# MotorController.net
KiCad netlist of a schematic drawn in EAGLE
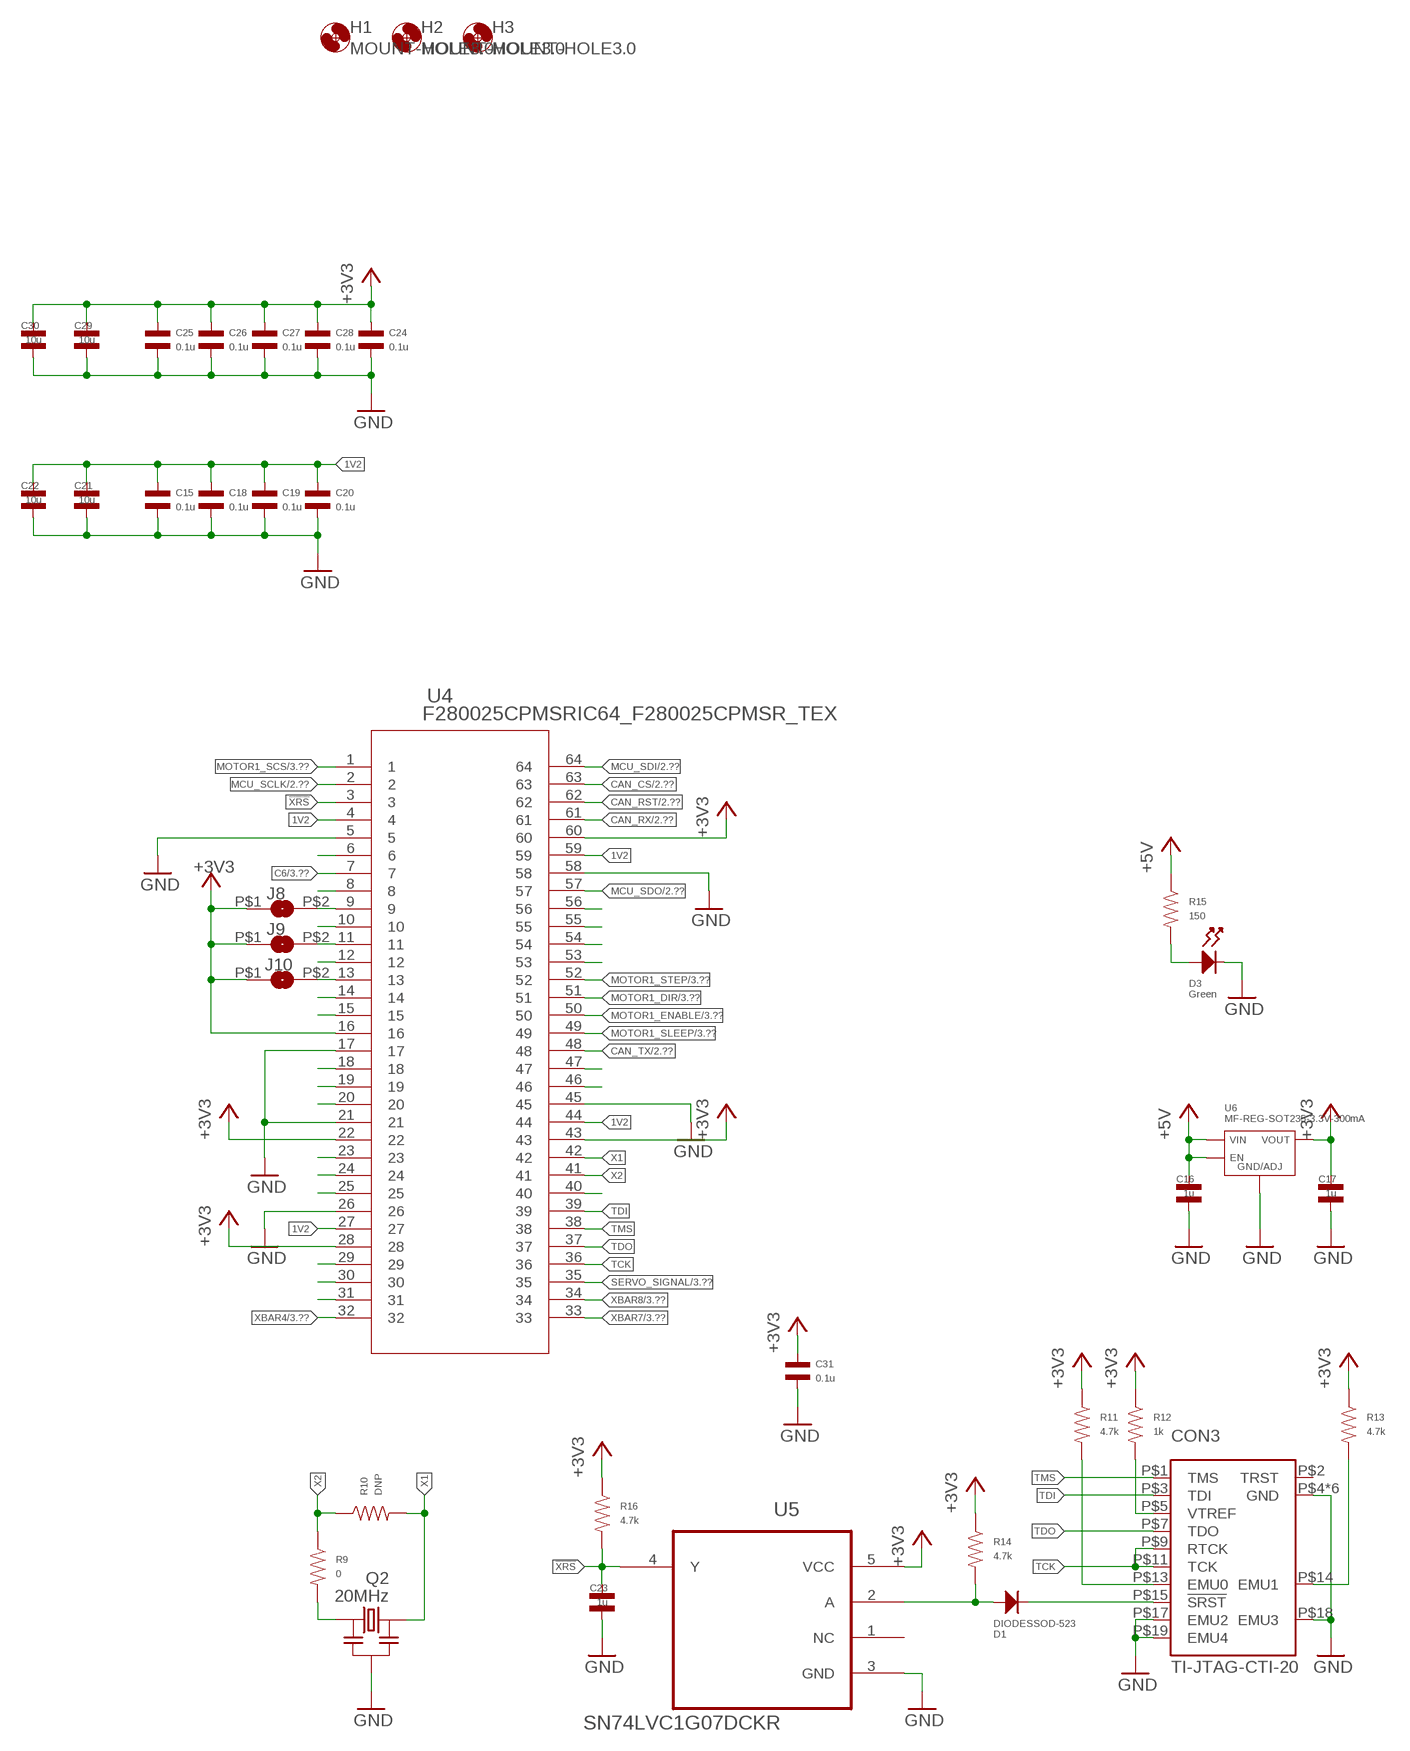
[diagram p0: schematic, sheet 1]
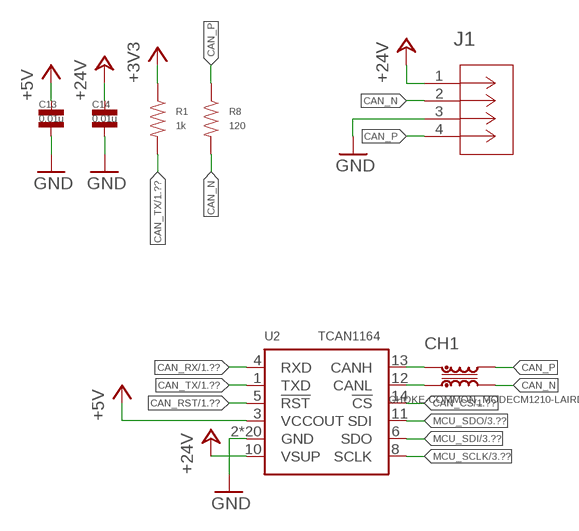
[diagram p1: schematic, sheet 2]
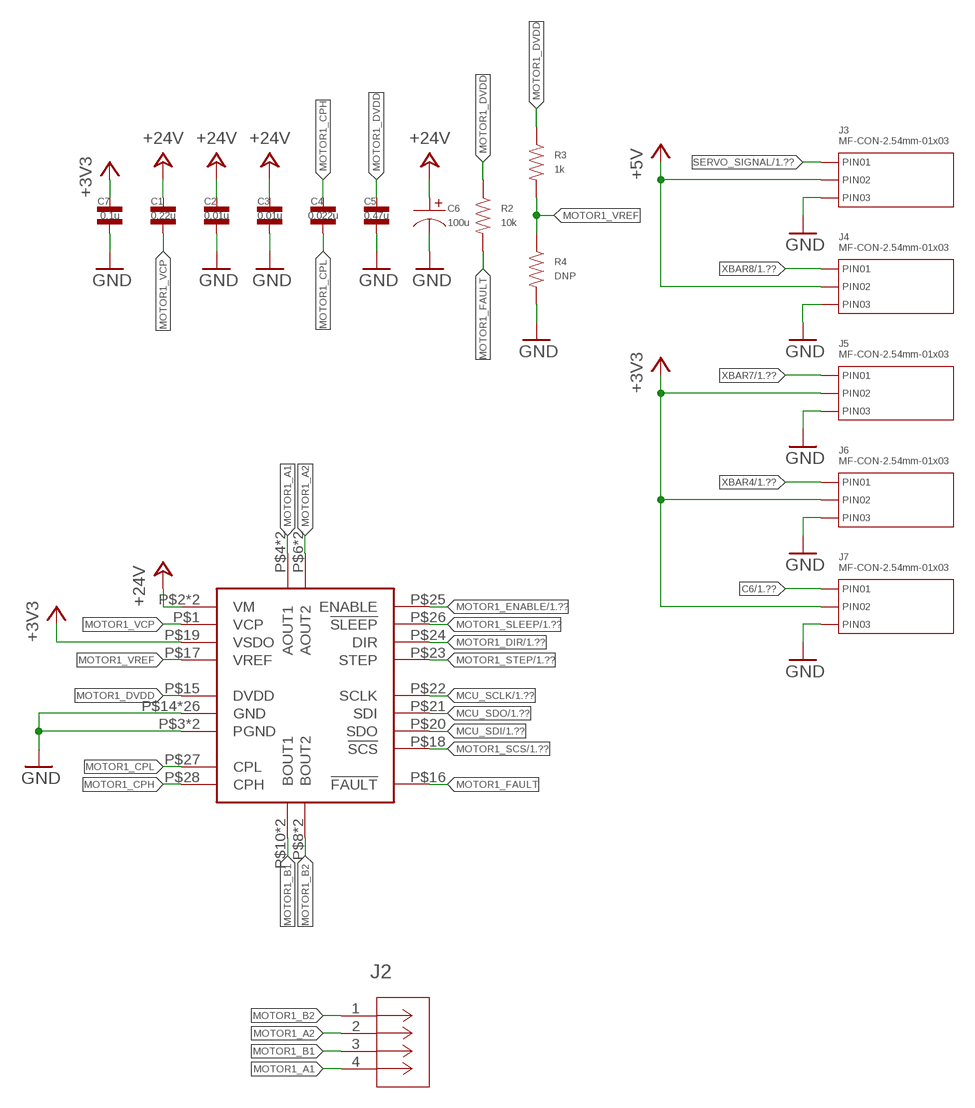
[diagram p2: schematic, sheet 3]

(export (version "E")
  (design (tool "Eeschema 10.0.6"))
  (components
    (comp (ref "C15")
      (value "0.1u")
      (footprint "eagle-import:C0402")
      (fields (field (name "MPN") "GCM155R71H104KE02D"))
      (libsource (lib "eagle-import") (part "CAPACITOR_NP_0402"))
    )
    (comp (ref "C16")
      (value "1u")
      (footprint "eagle-import:C0805")
      (fields (field (name "MPN") "CL21B105KAFNNNE"))
      (libsource (lib "eagle-import") (part "CAPACITOR_NP_0805"))
    )
    (comp (ref "C17")
      (value "1u")
      (footprint "eagle-import:C0805")
      (fields (field (name "MPN") "CL21B105KAFNNNE"))
      (libsource (lib "eagle-import") (part "CAPACITOR_NP_0805"))
    )
    (comp (ref "C18")
      (value "0.1u")
      (footprint "eagle-import:C0402")
      (fields (field (name "MPN") "GCM155R71H104KE02D"))
      (libsource (lib "eagle-import") (part "CAPACITOR_NP_0402"))
    )
    (comp (ref "C19")
      (value "0.1u")
      (footprint "eagle-import:C0402")
      (fields (field (name "MPN") "GCM155R71H104KE02D"))
      (libsource (lib "eagle-import") (part "CAPACITOR_NP_0402"))
    )
    (comp (ref "C20")
      (value "0.1u")
      (footprint "eagle-import:C0402")
      (fields (field (name "MPN") "GCM155R71H104KE02D"))
      (libsource (lib "eagle-import") (part "CAPACITOR_NP_0402"))
    )
    (comp (ref "C21")
      (value "10u")
      (footprint "eagle-import:C0805")
      (fields (field (name "MPN") "CL21A106KAYNNNE"))
      (libsource (lib "eagle-import") (part "CAPACITOR_NP_0805"))
    )
    (comp (ref "C22")
      (value "10u")
      (footprint "eagle-import:C0805")
      (fields (field (name "MPN") "CL21A106KAYNNNE"))
      (libsource (lib "eagle-import") (part "CAPACITOR_NP_0805"))
    )
    (comp (ref "C23")
      (value "1u")
      (footprint "eagle-import:C0402")
      (fields (field (name "MPN") "CL05A105KA5NQNC"))
      (libsource (lib "eagle-import") (part "CAPACITOR_NP_0402"))
    )
    (comp (ref "C24")
      (value "0.1u")
      (footprint "eagle-import:C0402")
      (fields (field (name "MPN") "GCM155R71H104KE02D"))
      (libsource (lib "eagle-import") (part "CAPACITOR_NP_0402"))
    )
    (comp (ref "C25")
      (value "0.1u")
      (footprint "eagle-import:C0402")
      (fields (field (name "MPN") "GCM155R71H104KE02D"))
      (libsource (lib "eagle-import") (part "CAPACITOR_NP_0402"))
    )
    (comp (ref "C26")
      (value "0.1u")
      (footprint "eagle-import:C0402")
      (fields (field (name "MPN") "GCM155R71H104KE02D"))
      (libsource (lib "eagle-import") (part "CAPACITOR_NP_0402"))
    )
    (comp (ref "C27")
      (value "0.1u")
      (footprint "eagle-import:C0402")
      (fields (field (name "MPN") "GCM155R71H104KE02D"))
      (libsource (lib "eagle-import") (part "CAPACITOR_NP_0402"))
    )
    (comp (ref "C28")
      (value "0.1u")
      (footprint "eagle-import:C0402")
      (fields (field (name "MPN") "GCM155R71H104KE02D"))
      (libsource (lib "eagle-import") (part "CAPACITOR_NP_0402"))
    )
    (comp (ref "C29")
      (value "10u")
      (footprint "eagle-import:C0805")
      (fields (field (name "MPN") "CL21A106KAYNNNE"))
      (libsource (lib "eagle-import") (part "CAPACITOR_NP_0805"))
    )
    (comp (ref "C30")
      (value "10u")
      (footprint "eagle-import:C0805")
      (fields (field (name "MPN") "CL21A106KAYNNNE"))
      (libsource (lib "eagle-import") (part "CAPACITOR_NP_0805"))
    )
    (comp (ref "C31")
      (value "0.1u")
      (footprint "eagle-import:C0402")
      (fields (field (name "MPN") "GCM155R71H104KE02D"))
      (libsource (lib "eagle-import") (part "MF_Passives_4704077_CAPACITOR_NP_0402"))
    )
    (comp (ref "CON3")
      (value "TI-JTAG-CTI-20")
      (footprint "eagle-import:FTR-110-51-L-D-06")
      (fields (field (name "MPN") "FTR-110-51-L-D-06"))
      (libsource (lib "eagle-import") (part "TI-JTAG-CTI-20"))
    )
    (comp (ref "D1")
      (value "DIODESSOD-523")
      (footprint "eagle-import:SOD523")
      (fields (field (name "MPN") "RB510SM-40FHT2R"))
      (libsource (lib "eagle-import") (part "DIODESSOD-523"))
    )
    (comp (ref "D3")
      (value "Green")
      (footprint "eagle-import:LED0603")
      (fields (field (name "HOUSEPART") "NO") (field (name "MPN") "SML-E12P8WT86"))
      (libsource (lib "eagle-import") (part "LED_SINGLE-0603"))
    )
    (comp (ref "H1")
      (value "MOUNT-HOLE3.0")
      (footprint "eagle-import:3,0")
      (libsource (lib "eagle-import") (part "MOUNT-HOLE3.0"))
    )
    (comp (ref "H2")
      (value "MOUNT-HOLE3.0")
      (footprint "eagle-import:3,0")
      (libsource (lib "eagle-import") (part "MOUNT-HOLE3.0"))
    )
    (comp (ref "H3")
      (value "MOUNT-HOLE3.0")
      (footprint "eagle-import:3,0")
      (libsource (lib "eagle-import") (part "MOUNT-HOLE3.0"))
    )
    (comp (ref "J8")
      (value "JUMPER")
      (footprint "eagle-import:SJ")
      (libsource (lib "eagle-import") (part "JUMPER"))
    )
    (comp (ref "J9")
      (value "JUMPER")
      (footprint "eagle-import:SJ")
      (libsource (lib "eagle-import") (part "JUMPER"))
    )
    (comp (ref "J10")
      (value "JUMPER")
      (footprint "eagle-import:SJ")
      (libsource (lib "eagle-import") (part "JUMPER"))
    )
    (comp (ref "Q2")
      (value "20MHz")
      (footprint "eagle-import:CSTNE")
      (fields (field (name "MPN") "CSTNE20M0V53C000R0"))
      (libsource (lib "eagle-import") (part "RESONATORCSTNE"))
    )
    (comp (ref "R9")
      (value "0")
      (footprint "eagle-import:R0402")
      (fields (field (name "MPN") "ERJ-2GE0R00X"))
      (libsource (lib "eagle-import") (part "RESISTOR_0402"))
    )
    (comp (ref "R10")
      (value "DNP")
      (footprint "eagle-import:R0402")
      (libsource (lib "eagle-import") (part "RESISTOR_0402"))
    )
    (comp (ref "R11")
      (value "4.7k")
      (footprint "eagle-import:R0402")
      (fields (field (name "MPN") "ERJ-2RKF4701X"))
      (libsource (lib "eagle-import") (part "RESISTOR_0402"))
    )
    (comp (ref "R12")
      (value "1k")
      (footprint "eagle-import:R0402")
      (fields (field (name "MPN") "ERJ-2RKF1001X"))
      (libsource (lib "eagle-import") (part "RESISTOR_0402"))
    )
    (comp (ref "R13")
      (value "4.7k")
      (footprint "eagle-import:R0402")
      (fields (field (name "MPN") "ERJ-2RKF4701X"))
      (libsource (lib "eagle-import") (part "RESISTOR_0402"))
    )
    (comp (ref "R14")
      (value "4.7k")
      (footprint "eagle-import:R0402")
      (fields (field (name "MPN") "ERJ-2RKF4701X"))
      (libsource (lib "eagle-import") (part "RESISTOR_0402"))
    )
    (comp (ref "R15")
      (value "150")
      (footprint "eagle-import:R0805")
      (fields (field (name "MPN") "ERJ-6GEYJ151V"))
      (libsource (lib "eagle-import") (part "RESISTOR_0805"))
    )
    (comp (ref "R16")
      (value "4.7k")
      (footprint "eagle-import:R0402")
      (fields (field (name "MPN") "ERJ-2RKF4701X"))
      (libsource (lib "eagle-import") (part "RESISTOR_0402"))
    )
    (comp (ref "U4")
      (value "F280025CPMSRIC64_F280025CPMSR_TEX")
      (footprint "eagle-import:IC64_F280025CPMSR_TEX")
      (fields
        (field (name "MANUFACTURER_PART_NUMBER") "F280025CPMSR")
        (field (name "COPYRIGHT") "Copyright (C) 2024 Ultra Librarian. All rights reserved.")
      )
      (libsource (lib "eagle-import") (part "F280025CPMSRIC64_F280025CPMSR_TEX"))
    )
    (comp (ref "U5")
      (value "SN74LVC1G07DCKR")
      (footprint "eagle-import:SOT65P210X110-5N")
      (libsource (lib "eagle-import") (part "SN74LVC1G07DCKR"))
    )
    (comp (ref "U6")
      (value "MF-REG-SOT235-3.3V-300mA")
      (footprint "eagle-import:SOT-23-5")
      (fields (field (name "HOUSEPART") "YES") (field (name "MPN") "TLV70233PDBVR"))
      (libsource (lib "eagle-import") (part "TLV70233PDBVR"))
    )
    (comp (ref "C13")
      (value "0.01u")
      (footprint "eagle-import:C0402")
      (fields (field (name "MPN") "CL05B103KB5NNNC"))
      (libsource (lib "eagle-import") (part "CAPACITOR_NP_0402"))
    )
    (comp (ref "C14")
      (value "0.01u")
      (footprint "eagle-import:C0402")
      (fields (field (name "MPN") "CL05B103KB5NNNC"))
      (libsource (lib "eagle-import") (part "CAPACITOR_NP_0402"))
    )
    (comp (ref "CH1")
      (value "CHOKE-COMMON_MODECM1210-LAIRD")
      (footprint "eagle-import:CM1210-LAIRD")
      (fields (field (name "MPN") "CM1210B104R-1A"))
      (libsource (lib "eagle-import") (part "CHOKE-COMMON_MODECM1210-LAIRD"))
    )
    (comp (ref "J1")
      (value "768250004CON_768250004_MOL")
      (footprint "eagle-import:CON_768250004_MOL")
      (fields
        (field (name "MANUFACTURER_PART_NUMBER") "768250004")
        (field (name "MPN") "0768250004")
        (field (name "COPYRIGHT") "Copyright (C) 2024 Ultra Librarian. All rights reserved.")
      )
      (libsource (lib "eagle-import") (part "768250004CON_768250004_MOL"))
    )
    (comp (ref "R1")
      (value "1k")
      (footprint "eagle-import:R0402")
      (fields (field (name "MPN") "ERJ-2RKF1001X"))
      (libsource (lib "eagle-import") (part "RESISTOR_0402"))
    )
    (comp (ref "R8")
      (value "120")
      (footprint "eagle-import:R0402")
      (fields (field (name "MPN") "ERJ-2GEJ121X"))
      (libsource (lib "eagle-import") (part "RESISTOR_0402"))
    )
    (comp (ref "U2")
      (value "TCAN1164")
      (footprint "eagle-import:CONV_TPS63021DSJ")
      (fields (field (name "MPN") "TCAN1164DMTRQ1"))
      (libsource (lib "eagle-import") (part "TCAN1164"))
    )
    (comp (ref "C1")
      (value "0.22u")
      (footprint "eagle-import:C0402")
      (fields (field (name "MPN") "CL05B224KA5VPNC"))
      (libsource (lib "eagle-import") (part "CAPACITOR_NP_0402"))
    )
    (comp (ref "C2")
      (value "0.01u")
      (footprint "eagle-import:C0402")
      (fields (field (name "MPN") "CL05B103KB5NNNC"))
      (libsource (lib "eagle-import") (part "CAPACITOR_NP_0402"))
    )
    (comp (ref "C3")
      (value "0.01u")
      (footprint "eagle-import:C0402")
      (fields (field (name "MPN") "CL05B103KB5NNNC"))
      (libsource (lib "eagle-import") (part "CAPACITOR_NP_0402"))
    )
    (comp (ref "C4")
      (value "0.022u")
      (footprint "eagle-import:C0402")
      (fields (field (name "MPN") "CL05B223KB5VPNC"))
      (libsource (lib "eagle-import") (part "CAPACITOR_NP_0402"))
    )
    (comp (ref "C5")
      (value "0.47u")
      (footprint "eagle-import:C0402")
      (fields (field (name "MPN") "CL05A474KA5NNNC"))
      (libsource (lib "eagle-import") (part "CAPACITOR_NP_0402"))
    )
    (comp (ref "C6")
      (value "100u")
      (footprint "eagle-import:CP6.3MM")
      (fields (field (name "MPN") "MAL218297603E3"))
      (libsource (lib "eagle-import") (part "CAPACITOR_P_6.3MM"))
    )
    (comp (ref "C7")
      (value "0.1u")
      (footprint "eagle-import:C0402")
      (fields (field (name "MPN") "GCM155R71H104KE02D"))
      (libsource (lib "eagle-import") (part "CAPACITOR_NP_0402"))
    )
    (comp (ref "J2")
      (value "768250004CON_768250004_MOL")
      (footprint "eagle-import:CON_768250004_MOL")
      (fields
        (field (name "MANUFACTURER_PART_NUMBER") "768250004")
        (field (name "MPN") "0768250004")
        (field (name "COPYRIGHT") "Copyright (C) 2024 Ultra Librarian. All rights reserved.")
      )
      (libsource (lib "eagle-import") (part "768250004CON_768250004_MOL"))
    )
    (comp (ref "J3")
      (value "MF-CON-2.54mm-01x03")
      (footprint "eagle-import:PTH_2.54MM_01X03")
      (fields (field (name "HOUSEPART") "YES"))
      (libsource (lib "eagle-import") (part "CON_01X03_PTH_2.54MM"))
    )
    (comp (ref "J4")
      (value "MF-CON-2.54mm-01x03")
      (footprint "eagle-import:PTH_2.54MM_01X03")
      (fields (field (name "HOUSEPART") "YES"))
      (libsource (lib "eagle-import") (part "CON_01X03_PTH_2.54MM"))
    )
    (comp (ref "J5")
      (value "MF-CON-2.54mm-01x03")
      (footprint "eagle-import:PTH_2.54MM_01X03")
      (fields (field (name "HOUSEPART") "YES"))
      (libsource (lib "eagle-import") (part "CON_01X03_PTH_2.54MM"))
    )
    (comp (ref "J6")
      (value "MF-CON-2.54mm-01x03")
      (footprint "eagle-import:PTH_2.54MM_01X03")
      (fields (field (name "HOUSEPART") "YES"))
      (libsource (lib "eagle-import") (part "CON_01X03_PTH_2.54MM"))
    )
    (comp (ref "J7")
      (value "MF-CON-2.54mm-01x03")
      (footprint "eagle-import:PTH_2.54MM_01X03")
      (fields (field (name "HOUSEPART") "YES"))
      (libsource (lib "eagle-import") (part "CON_01X03_PTH_2.54MM"))
    )
    (comp (ref "R2")
      (value "10k")
      (footprint "eagle-import:R0402")
      (fields (field (name "MPN") "ERJ-2RKF1002X"))
      (libsource (lib "eagle-import") (part "RESISTOR_0402"))
    )
    (comp (ref "R3")
      (value "1k")
      (footprint "eagle-import:R0402")
      (fields (field (name "MPN") "ERJ-2RKF1001X"))
      (libsource (lib "eagle-import") (part "RESISTOR_0402"))
    )
    (comp (ref "R4")
      (value "DNP")
      (footprint "eagle-import:R0402")
      (libsource (lib "eagle-import") (part "RESISTOR_0402"))
    )
    (comp (ref "U1")
      (value "DRV8434SPWPR")
      (footprint "eagle-import:HTSSOP(PWP)-28")
      (libsource (lib "eagle-import") (part "DRV8434SPWPR"))
    )
  )
  (nets
    (net (code "1") (name "+3V3") (class "Default")
      (node (ref "C17") (pin "P$1") (pinfunction "P$1_P$1") (pintype "passive"))
      (node (ref "C24") (pin "P$1") (pinfunction "P$1_P$1") (pintype "passive"))
      (node (ref "C25") (pin "P$1") (pinfunction "P$1_P$1") (pintype "passive"))
      (node (ref "C26") (pin "P$1") (pinfunction "P$1_P$1") (pintype "passive"))
      (node (ref "C27") (pin "P$1") (pinfunction "P$1_P$1") (pintype "passive"))
      (node (ref "C28") (pin "P$1") (pinfunction "P$1_P$1") (pintype "passive"))
      (node (ref "C29") (pin "P$1") (pinfunction "P$1_P$1") (pintype "passive"))
      (node (ref "C30") (pin "P$1") (pinfunction "P$1_P$1") (pintype "passive"))
      (node (ref "C31") (pin "P$1") (pinfunction "P$1_P$1") (pintype "passive"))
      (node (ref "C7") (pin "P$1") (pinfunction "P$1_P$1") (pintype "passive"))
      (node (ref "J10") (pin "P$1") (pinfunction "1_P$1") (pintype "passive"))
      (node (ref "J5") (pin "P$2") (pinfunction "PIN2_P$2") (pintype "bidirectional"))
      (node (ref "J6") (pin "P$2") (pinfunction "PIN2_P$2") (pintype "bidirectional"))
      (node (ref "J7") (pin "P$2") (pinfunction "PIN2_P$2") (pintype "bidirectional"))
      (node (ref "J8") (pin "P$1") (pinfunction "1_P$1") (pintype "passive"))
      (node (ref "J9") (pin "P$1") (pinfunction "1_P$1") (pintype "passive"))
      (node (ref "R1") (pin "P$1") (pinfunction "P$1_P$1") (pintype "passive"))
      (node (ref "R11") (pin "P$1") (pinfunction "P$1_P$1") (pintype "passive"))
      (node (ref "R12") (pin "P$1") (pinfunction "P$1_P$1") (pintype "passive"))
      (node (ref "R13") (pin "P$1") (pinfunction "P$1_P$1") (pintype "passive"))
      (node (ref "R14") (pin "P$1") (pinfunction "P$1_P$1") (pintype "passive"))
      (node (ref "R16") (pin "P$1") (pinfunction "P$1_P$1") (pintype "passive"))
      (node (ref "U1") (pin "P$19") (pinfunction "VSDO_P$19") (pintype "bidirectional"))
      (node (ref "U4") (pin "16") (pinfunction "16_16") (pintype "passive"))
      (node (ref "U4") (pin "22") (pinfunction "22_22") (pintype "passive"))
      (node (ref "U4") (pin "28") (pinfunction "28_28") (pintype "passive"))
      (node (ref "U4") (pin "43") (pinfunction "43_43") (pintype "passive"))
      (node (ref "U4") (pin "60") (pinfunction "60_60") (pintype "passive"))
      (node (ref "U5") (pin "5") (pinfunction "VCC_5") (pintype "power_in"))
      (node (ref "U6") (pin "P$5") (pinfunction "VOUT_P$5") (pintype "bidirectional"))
    )
    (net (code "2") (name "+5V") (class "Default")
      (node (ref "C13") (pin "P$1") (pinfunction "P$1_P$1") (pintype "passive"))
      (node (ref "C16") (pin "P$1") (pinfunction "P$1_P$1") (pintype "passive"))
      (node (ref "J3") (pin "P$2") (pinfunction "PIN2_P$2") (pintype "bidirectional"))
      (node (ref "J4") (pin "P$2") (pinfunction "PIN2_P$2") (pintype "bidirectional"))
      (node (ref "R15") (pin "P$1") (pinfunction "P$1_P$1") (pintype "passive"))
      (node (ref "U2") (pin "3") (pinfunction "VCCOUT_3") (pintype "bidirectional"))
      (node (ref "U6") (pin "P$1") (pinfunction "VIN_P$1") (pintype "bidirectional"))
      (node (ref "U6") (pin "P$3") (pinfunction "EN_P$3") (pintype "bidirectional"))
    )
    (net (code "3") (name "+24V") (class "Default")
      (node (ref "C1") (pin "P$1") (pinfunction "P$1_P$1") (pintype "passive"))
      (node (ref "C14") (pin "P$1") (pinfunction "P$1_P$1") (pintype "passive"))
      (node (ref "C2") (pin "P$1") (pinfunction "P$1_P$1") (pintype "passive"))
      (node (ref "C3") (pin "P$1") (pinfunction "P$1_P$1") (pintype "passive"))
      (node (ref "C6") (pin "P$1") (pinfunction "P$1_P$1") (pintype "passive"))
      (node (ref "J1") (pin "1") (pinfunction "1_1") (pintype "passive"))
      (node (ref "U1") (pin "P$13") (pinfunction "VM_P$13") (pintype "bidirectional"))
      (node (ref "U1") (pin "P$2") (pinfunction "VM_P$2") (pintype "bidirectional"))
      (node (ref "U2") (pin "10") (pinfunction "VSUP_10") (pintype "bidirectional"))
    )
    (net (code "4") (name "1V2") (class "Default")
      (node (ref "C15") (pin "P$1") (pinfunction "P$1_P$1") (pintype "passive"))
      (node (ref "C18") (pin "P$1") (pinfunction "P$1_P$1") (pintype "passive"))
      (node (ref "C19") (pin "P$1") (pinfunction "P$1_P$1") (pintype "passive"))
      (node (ref "C20") (pin "P$1") (pinfunction "P$1_P$1") (pintype "passive"))
      (node (ref "C21") (pin "P$1") (pinfunction "P$1_P$1") (pintype "passive"))
      (node (ref "C22") (pin "P$1") (pinfunction "P$1_P$1") (pintype "passive"))
      (node (ref "U4") (pin "27") (pinfunction "27_27") (pintype "passive"))
      (node (ref "U4") (pin "4") (pinfunction "4_4") (pintype "passive"))
      (node (ref "U4") (pin "44") (pinfunction "44_44") (pintype "passive"))
      (node (ref "U4") (pin "59") (pinfunction "59_59") (pintype "passive"))
    )
    (net (code "5") (name "C6") (class "Default")
      (node (ref "J7") (pin "P$1") (pinfunction "PIN1_P$1") (pintype "bidirectional"))
      (node (ref "U4") (pin "7") (pinfunction "7_7") (pintype "passive"))
    )
    (net (code "6") (name "CAN_CS") (class "Default")
      (node (ref "U2") (pin "14") (pinfunction "~{CS}_14") (pintype "bidirectional"))
      (node (ref "U4") (pin "63") (pinfunction "63_63") (pintype "passive"))
    )
    (net (code "7") (name "CAN_N") (class "Default")
      (node (ref "CH1") (pin "P$3") (pinfunction "3_P$3") (pintype "bidirectional"))
      (node (ref "J1") (pin "2") (pinfunction "2_2") (pintype "passive"))
      (node (ref "R8") (pin "P$2") (pinfunction "P$2_P$2") (pintype "passive"))
    )
    (net (code "8") (name "CAN_P") (class "Default")
      (node (ref "CH1") (pin "P$2") (pinfunction "2_P$2") (pintype "bidirectional"))
      (node (ref "J1") (pin "4") (pinfunction "4_4") (pintype "passive"))
      (node (ref "R8") (pin "P$1") (pinfunction "P$1_P$1") (pintype "passive"))
    )
    (net (code "9") (name "CAN_RST") (class "Default")
      (node (ref "U2") (pin "5") (pinfunction "~{RST}_5") (pintype "bidirectional"))
      (node (ref "U4") (pin "62") (pinfunction "62_62") (pintype "passive"))
    )
    (net (code "10") (name "CAN_RX") (class "Default")
      (node (ref "U2") (pin "4") (pinfunction "RXD_4") (pintype "bidirectional"))
      (node (ref "U4") (pin "61") (pinfunction "61_61") (pintype "passive"))
    )
    (net (code "11") (name "CAN_TX") (class "Default")
      (node (ref "R1") (pin "P$2") (pinfunction "P$2_P$2") (pintype "passive"))
      (node (ref "U2") (pin "1") (pinfunction "TXD_1") (pintype "bidirectional"))
      (node (ref "U4") (pin "48") (pinfunction "48_48") (pintype "passive"))
    )
    (net (code "12") (name "GND") (class "Default")
      (node (ref "C13") (pin "P$2") (pinfunction "P$2_P$2") (pintype "passive"))
      (node (ref "C14") (pin "P$2") (pinfunction "P$2_P$2") (pintype "passive"))
      (node (ref "C15") (pin "P$2") (pinfunction "P$2_P$2") (pintype "passive"))
      (node (ref "C16") (pin "P$2") (pinfunction "P$2_P$2") (pintype "passive"))
      (node (ref "C17") (pin "P$2") (pinfunction "P$2_P$2") (pintype "passive"))
      (node (ref "C18") (pin "P$2") (pinfunction "P$2_P$2") (pintype "passive"))
      (node (ref "C19") (pin "P$2") (pinfunction "P$2_P$2") (pintype "passive"))
      (node (ref "C2") (pin "P$2") (pinfunction "P$2_P$2") (pintype "passive"))
      (node (ref "C20") (pin "P$2") (pinfunction "P$2_P$2") (pintype "passive"))
      (node (ref "C21") (pin "P$2") (pinfunction "P$2_P$2") (pintype "passive"))
      (node (ref "C22") (pin "P$2") (pinfunction "P$2_P$2") (pintype "passive"))
      (node (ref "C23") (pin "P$2") (pinfunction "P$2_P$2") (pintype "passive"))
      (node (ref "C24") (pin "P$2") (pinfunction "P$2_P$2") (pintype "passive"))
      (node (ref "C25") (pin "P$2") (pinfunction "P$2_P$2") (pintype "passive"))
      (node (ref "C26") (pin "P$2") (pinfunction "P$2_P$2") (pintype "passive"))
      (node (ref "C27") (pin "P$2") (pinfunction "P$2_P$2") (pintype "passive"))
      (node (ref "C28") (pin "P$2") (pinfunction "P$2_P$2") (pintype "passive"))
      (node (ref "C29") (pin "P$2") (pinfunction "P$2_P$2") (pintype "passive"))
      (node (ref "C3") (pin "P$2") (pinfunction "P$2_P$2") (pintype "passive"))
      (node (ref "C30") (pin "P$2") (pinfunction "P$2_P$2") (pintype "passive"))
      (node (ref "C31") (pin "P$2") (pinfunction "P$2_P$2") (pintype "passive"))
      (node (ref "C5") (pin "P$2") (pinfunction "P$2_P$2") (pintype "passive"))
      (node (ref "C6") (pin "P$2") (pinfunction "P$2_P$2") (pintype "passive"))
      (node (ref "C7") (pin "P$2") (pinfunction "P$2_P$2") (pintype "passive"))
      (node (ref "CON3") (pin "P$10") (pinfunction "GND_P$10") (pintype "bidirectional"))
      (node (ref "CON3") (pin "P$12") (pinfunction "GND_P$12") (pintype "bidirectional"))
      (node (ref "CON3") (pin "P$16") (pinfunction "GND_P$16") (pintype "bidirectional"))
      (node (ref "CON3") (pin "P$17") (pinfunction "EMU2_P$17") (pintype "bidirectional"))
      (node (ref "CON3") (pin "P$18") (pinfunction "EMU3_P$18") (pintype "bidirectional"))
      (node (ref "CON3") (pin "P$19") (pinfunction "EMU4_P$19") (pintype "bidirectional"))
      (node (ref "CON3") (pin "P$20") (pinfunction "GND_P$20") (pintype "bidirectional"))
      (node (ref "CON3") (pin "P$4") (pinfunction "GND_P$4") (pintype "bidirectional"))
      (node (ref "CON3") (pin "P$8") (pinfunction "GND_P$8") (pintype "bidirectional"))
      (node (ref "D3") (pin "CATHODE") (pinfunction "CATHODE_CATHODE") (pintype "power_in"))
      (node (ref "J1") (pin "3") (pinfunction "3_3") (pintype "passive"))
      (node (ref "J3") (pin "P$3") (pinfunction "PIN3_P$3") (pintype "bidirectional"))
      (node (ref "J4") (pin "P$3") (pinfunction "PIN3_P$3") (pintype "bidirectional"))
      (node (ref "J5") (pin "P$3") (pinfunction "PIN3_P$3") (pintype "bidirectional"))
      (node (ref "J6") (pin "P$3") (pinfunction "PIN3_P$3") (pintype "bidirectional"))
      (node (ref "J7") (pin "P$3") (pinfunction "PIN3_P$3") (pintype "bidirectional"))
      (node (ref "Q2") (pin "2") (pinfunction "GND_2") (pintype "passive"))
      (node (ref "R4") (pin "P$2") (pinfunction "P$2_P$2") (pintype "passive"))
      (node (ref "U1") (pin "P$12") (pinfunction "PGND_P$12") (pintype "bidirectional"))
      (node (ref "U1") (pin "P$14") (pinfunction "GND_P$14") (pintype "bidirectional"))
      (node (ref "U1") (pin "P$29") (pinfunction "GND_P$29") (pintype "bidirectional"))
      (node (ref "U1") (pin "P$3") (pinfunction "PGND_P$3") (pintype "bidirectional"))
      (node (ref "U1") (pin "P$30") (pinfunction "GND_P$30") (pintype "bidirectional"))
      (node (ref "U1") (pin "P$31") (pinfunction "GND_P$31") (pintype "bidirectional"))
      (node (ref "U1") (pin "P$32") (pinfunction "GND_P$32") (pintype "bidirectional"))
      (node (ref "U1") (pin "P$33") (pinfunction "GND_P$33") (pintype "bidirectional"))
      (node (ref "U1") (pin "P$34") (pinfunction "GND_P$34") (pintype "bidirectional"))
      (node (ref "U1") (pin "P$35") (pinfunction "GND_P$35") (pintype "bidirectional"))
      (node (ref "U1") (pin "P$36") (pinfunction "GND_P$36") (pintype "bidirectional"))
      (node (ref "U1") (pin "P$37") (pinfunction "GND_P$37") (pintype "bidirectional"))
      (node (ref "U1") (pin "P$38") (pinfunction "GND_P$38") (pintype "bidirectional"))
      (node (ref "U1") (pin "P$39") (pinfunction "GND_P$39") (pintype "bidirectional"))
      (node (ref "U1") (pin "P$40") (pinfunction "GND_P$40") (pintype "bidirectional"))
      (node (ref "U1") (pin "P$41") (pinfunction "GND_P$41") (pintype "bidirectional"))
      (node (ref "U1") (pin "P$42") (pinfunction "GND_P$42") (pintype "bidirectional"))
      (node (ref "U1") (pin "P$43") (pinfunction "GND_P$43") (pintype "bidirectional"))
      (node (ref "U1") (pin "P$44") (pinfunction "GND_P$44") (pintype "bidirectional"))
      (node (ref "U1") (pin "P$45") (pinfunction "GND_P$45") (pintype "bidirectional"))
      (node (ref "U1") (pin "P$46") (pinfunction "GND_P$46") (pintype "bidirectional"))
      (node (ref "U1") (pin "P$47") (pinfunction "GND_P$47") (pintype "bidirectional"))
      (node (ref "U1") (pin "P$48") (pinfunction "GND_P$48") (pintype "bidirectional"))
      (node (ref "U1") (pin "P$49") (pinfunction "GND_P$49") (pintype "bidirectional"))
      (node (ref "U1") (pin "P$50") (pinfunction "GND_P$50") (pintype "bidirectional"))
      (node (ref "U1") (pin "P$51") (pinfunction "GND_P$51") (pintype "bidirectional"))
      (node (ref "U1") (pin "P$52") (pinfunction "GND_P$52") (pintype "bidirectional"))
      (node (ref "U1") (pin "P$53") (pinfunction "GND_P$53") (pintype "bidirectional"))
      (node (ref "U2") (pin "15") (pinfunction "GND_15") (pintype "bidirectional"))
      (node (ref "U2") (pin "15_1") (pinfunction "GND_15_1") (pintype "bidirectional"))
      (node (ref "U2") (pin "15_10") (pinfunction "GND_15_10") (pintype "bidirectional"))
      (node (ref "U2") (pin "15_11") (pinfunction "GND_15_11") (pintype "bidirectional"))
      (node (ref "U2") (pin "15_12") (pinfunction "GND_15_12") (pintype "bidirectional"))
      (node (ref "U2") (pin "15_15") (pinfunction "GND_15_15") (pintype "bidirectional"))
      (node (ref "U2") (pin "15_16") (pinfunction "GND_15_16") (pintype "bidirectional"))
      (node (ref "U2") (pin "15_17") (pinfunction "GND_15_17") (pintype "bidirectional"))
      (node (ref "U2") (pin "15_2") (pinfunction "GND_15_2") (pintype "bidirectional"))
      (node (ref "U2") (pin "15_21") (pinfunction "GND_15_21") (pintype "bidirectional"))
      (node (ref "U2") (pin "15_22") (pinfunction "GND_15_22") (pintype "bidirectional"))
      (node (ref "U2") (pin "15_23") (pinfunction "GND_15_23") (pintype "bidirectional"))
      (node (ref "U2") (pin "15_3") (pinfunction "GND_15_3") (pintype "bidirectional"))
      (node (ref "U2") (pin "15_4") (pinfunction "GND_15_4") (pintype "bidirectional"))
      (node (ref "U2") (pin "15_5") (pinfunction "GND_15_5") (pintype "bidirectional"))
      (node (ref "U2") (pin "15_6") (pinfunction "GND_15_6") (pintype "bidirectional"))
      (node (ref "U2") (pin "15_7") (pinfunction "GND_15_7") (pintype "bidirectional"))
      (node (ref "U2") (pin "15_8") (pinfunction "GND_15_8") (pintype "bidirectional"))
      (node (ref "U2") (pin "15_9") (pinfunction "GND_15_9") (pintype "bidirectional"))
      (node (ref "U2") (pin "2") (pinfunction "GND_2") (pintype "bidirectional"))
      (node (ref "U4") (pin "17") (pinfunction "17_17") (pintype "passive"))
      (node (ref "U4") (pin "21") (pinfunction "21_21") (pintype "passive"))
      (node (ref "U4") (pin "26") (pinfunction "26_26") (pintype "passive"))
      (node (ref "U4") (pin "45") (pinfunction "45_45") (pintype "passive"))
      (node (ref "U4") (pin "5") (pinfunction "5_5") (pintype "passive"))
      (node (ref "U4") (pin "58") (pinfunction "58_58") (pintype "passive"))
      (node (ref "U5") (pin "3") (pinfunction "GND_3") (pintype "passive"))
      (node (ref "U6") (pin "P$2") (pinfunction "GND/ADJ_P$2") (pintype "bidirectional"))
    )
    (net (code "13") (name "MCU_SCLK") (class "Default")
      (node (ref "U1") (pin "P$22") (pinfunction "SCLK_P$22") (pintype "bidirectional"))
      (node (ref "U2") (pin "8") (pinfunction "SCLK_8") (pintype "bidirectional"))
      (node (ref "U4") (pin "2") (pinfunction "2_2") (pintype "passive"))
    )
    (net (code "14") (name "MCU_SDI") (class "Default")
      (node (ref "U1") (pin "P$20") (pinfunction "SDO_P$20") (pintype "bidirectional"))
      (node (ref "U2") (pin "6") (pinfunction "SDO_6") (pintype "bidirectional"))
      (node (ref "U4") (pin "64") (pinfunction "64_64") (pintype "passive"))
    )
    (net (code "15") (name "MCU_SDO") (class "Default")
      (node (ref "U1") (pin "P$21") (pinfunction "SDI_P$21") (pintype "bidirectional"))
      (node (ref "U2") (pin "11") (pinfunction "SDI_11") (pintype "bidirectional"))
      (node (ref "U4") (pin "57") (pinfunction "57_57") (pintype "passive"))
    )
    (net (code "16") (name "MOTOR1_A1") (class "Default")
      (node (ref "J2") (pin "4") (pinfunction "4_4") (pintype "passive"))
      (node (ref "U1") (pin "P$4") (pinfunction "AOUT1_P$4") (pintype "bidirectional"))
      (node (ref "U1") (pin "P$5") (pinfunction "AOUT1_P$5") (pintype "bidirectional"))
    )
    (net (code "17") (name "MOTOR1_A2") (class "Default")
      (node (ref "J2") (pin "2") (pinfunction "2_2") (pintype "passive"))
      (node (ref "U1") (pin "P$6") (pinfunction "AOUT2_P$6") (pintype "bidirectional"))
      (node (ref "U1") (pin "P$7") (pinfunction "AOUT2_P$7") (pintype "bidirectional"))
    )
    (net (code "18") (name "MOTOR1_B1") (class "Default")
      (node (ref "J2") (pin "3") (pinfunction "3_3") (pintype "passive"))
      (node (ref "U1") (pin "P$10") (pinfunction "BOUT1_P$10") (pintype "bidirectional"))
      (node (ref "U1") (pin "P$11") (pinfunction "BOUT1_P$11") (pintype "bidirectional"))
    )
    (net (code "19") (name "MOTOR1_B2") (class "Default")
      (node (ref "J2") (pin "1") (pinfunction "1_1") (pintype "passive"))
      (node (ref "U1") (pin "P$8") (pinfunction "BOUT2_P$8") (pintype "bidirectional"))
      (node (ref "U1") (pin "P$9") (pinfunction "BOUT2_P$9") (pintype "bidirectional"))
    )
    (net (code "20") (name "MOTOR1_CPH") (class "Default")
      (node (ref "C4") (pin "P$1") (pinfunction "P$1_P$1") (pintype "passive"))
      (node (ref "U1") (pin "P$28") (pinfunction "CPH_P$28") (pintype "bidirectional"))
    )
    (net (code "21") (name "MOTOR1_CPL") (class "Default")
      (node (ref "C4") (pin "P$2") (pinfunction "P$2_P$2") (pintype "passive"))
      (node (ref "U1") (pin "P$27") (pinfunction "CPL_P$27") (pintype "bidirectional"))
    )
    (net (code "22") (name "MOTOR1_DIR") (class "Default")
      (node (ref "U1") (pin "P$24") (pinfunction "DIR_P$24") (pintype "bidirectional"))
      (node (ref "U4") (pin "51") (pinfunction "51_51") (pintype "passive"))
    )
    (net (code "23") (name "MOTOR1_DVDD") (class "Default")
      (node (ref "C5") (pin "P$1") (pinfunction "P$1_P$1") (pintype "passive"))
      (node (ref "R2") (pin "P$1") (pinfunction "P$1_P$1") (pintype "passive"))
      (node (ref "R3") (pin "P$1") (pinfunction "P$1_P$1") (pintype "passive"))
      (node (ref "U1") (pin "P$15") (pinfunction "DVDD_P$15") (pintype "bidirectional"))
    )
    (net (code "24") (name "MOTOR1_ENABLE") (class "Default")
      (node (ref "U1") (pin "P$25") (pinfunction "ENABLE_P$25") (pintype "bidirectional"))
      (node (ref "U4") (pin "50") (pinfunction "50_50") (pintype "passive"))
    )
    (net (code "25") (name "MOTOR1_FAULT") (class "Default")
      (node (ref "R2") (pin "P$2") (pinfunction "P$2_P$2") (pintype "passive"))
      (node (ref "U1") (pin "P$16") (pinfunction "~{FAULT}_P$16") (pintype "bidirectional"))
    )
    (net (code "26") (name "MOTOR1_SCS") (class "Default")
      (node (ref "U1") (pin "P$18") (pinfunction "~{SCS}_P$18") (pintype "bidirectional"))
      (node (ref "U4") (pin "1") (pinfunction "1_1") (pintype "passive"))
    )
    (net (code "27") (name "MOTOR1_SLEEP") (class "Default")
      (node (ref "U1") (pin "P$26") (pinfunction "~{SLEEP}_P$26") (pintype "bidirectional"))
      (node (ref "U4") (pin "49") (pinfunction "49_49") (pintype "passive"))
    )
    (net (code "28") (name "MOTOR1_STEP") (class "Default")
      (node (ref "U1") (pin "P$23") (pinfunction "STEP_P$23") (pintype "bidirectional"))
      (node (ref "U4") (pin "52") (pinfunction "52_52") (pintype "passive"))
    )
    (net (code "29") (name "MOTOR1_VCP") (class "Default")
      (node (ref "C1") (pin "P$2") (pinfunction "P$2_P$2") (pintype "passive"))
      (node (ref "U1") (pin "P$1") (pinfunction "VCP_P$1") (pintype "bidirectional"))
    )
    (net (code "30") (name "MOTOR1_VREF") (class "Default")
      (node (ref "R3") (pin "P$2") (pinfunction "P$2_P$2") (pintype "passive"))
      (node (ref "R4") (pin "P$1") (pinfunction "P$1_P$1") (pintype "passive"))
      (node (ref "U1") (pin "P$17") (pinfunction "VREF_P$17") (pintype "bidirectional"))
    )
    (net (code "31") (name "Net-(CH1-1)") (class "Default")
      (node (ref "CH1") (pin "P$1") (pinfunction "1_P$1") (pintype "bidirectional"))
      (node (ref "U2") (pin "13") (pinfunction "CANH_13") (pintype "bidirectional"))
    )
    (net (code "32") (name "Net-(CH1-4)") (class "Default")
      (node (ref "CH1") (pin "P$4") (pinfunction "4_P$4") (pintype "bidirectional"))
      (node (ref "U2") (pin "12") (pinfunction "CANL_12") (pintype "bidirectional"))
    )
    (net (code "33") (name "Net-(CON3-EMU0)") (class "Default")
      (node (ref "CON3") (pin "P$13") (pinfunction "EMU0_P$13") (pintype "bidirectional"))
      (node (ref "R11") (pin "P$2") (pinfunction "P$2_P$2") (pintype "passive"))
    )
    (net (code "34") (name "Net-(CON3-EMU1)") (class "Default")
      (node (ref "CON3") (pin "P$14") (pinfunction "EMU1_P$14") (pintype "bidirectional"))
      (node (ref "R13") (pin "P$2") (pinfunction "P$2_P$2") (pintype "passive"))
    )
    (net (code "35") (name "Net-(CON3-VTREF)") (class "Default")
      (node (ref "CON3") (pin "P$5") (pinfunction "VTREF_P$5") (pintype "bidirectional"))
      (node (ref "R12") (pin "P$2") (pinfunction "P$2_P$2") (pintype "passive"))
    )
    (net (code "36") (name "Net-(CON3-~{SRST})") (class "Default")
      (node (ref "CON3") (pin "P$15") (pinfunction "~{SRST}_P$15") (pintype "bidirectional"))
      (node (ref "D1") (pin "C") (pinfunction "CATHODE_C") (pintype "bidirectional"))
    )
    (net (code "37") (name "Net-(D1-ANODE)") (class "Default")
      (node (ref "D1") (pin "A") (pinfunction "ANODE_A") (pintype "bidirectional"))
      (node (ref "R14") (pin "P$2") (pinfunction "P$2_P$2") (pintype "passive"))
      (node (ref "U5") (pin "2") (pinfunction "A_2") (pintype "input"))
    )
    (net (code "38") (name "Net-(D3-PadANODE)") (class "Default")
      (node (ref "D3") (pin "ANODE") (pinfunction "ANODE_ANODE") (pintype "power_in"))
      (node (ref "R15") (pin "P$2") (pinfunction "P$2_P$2") (pintype "passive"))
    )
    (net (code "39") (name "Net-(J8-2)") (class "Default")
      (node (ref "J8") (pin "P$2") (pinfunction "2_P$2") (pintype "passive"))
      (node (ref "U4") (pin "9") (pinfunction "9_9") (pintype "passive"))
    )
    (net (code "40") (name "Net-(J9-2)") (class "Default")
      (node (ref "J9") (pin "P$2") (pinfunction "2_P$2") (pintype "passive"))
      (node (ref "U4") (pin "11") (pinfunction "11_11") (pintype "passive"))
    )
    (net (code "41") (name "Net-(J10-2)") (class "Default")
      (node (ref "J10") (pin "P$2") (pinfunction "2_P$2") (pintype "passive"))
      (node (ref "U4") (pin "13") (pinfunction "13_13") (pintype "passive"))
    )
    (net (code "42") (name "Net-(Q2-XOUT)") (class "Default")
      (node (ref "Q2") (pin "3") (pinfunction "XOUT_3") (pintype "passive"))
      (node (ref "R9") (pin "P$2") (pinfunction "P$2_P$2") (pintype "passive"))
    )
    (net (code "43") (name "SERVO_SIGNAL") (class "Default")
      (node (ref "J3") (pin "P$1") (pinfunction "PIN1_P$1") (pintype "bidirectional"))
      (node (ref "U4") (pin "35") (pinfunction "35_35") (pintype "passive"))
    )
    (net (code "44") (name "TCK") (class "Default")
      (node (ref "CON3") (pin "P$11") (pinfunction "TCK_P$11") (pintype "bidirectional"))
      (node (ref "CON3") (pin "P$9") (pinfunction "RTCK_P$9") (pintype "bidirectional"))
      (node (ref "U4") (pin "36") (pinfunction "36_36") (pintype "passive"))
    )
    (net (code "45") (name "TDI") (class "Default")
      (node (ref "CON3") (pin "P$3") (pinfunction "TDI_P$3") (pintype "bidirectional"))
      (node (ref "U4") (pin "39") (pinfunction "39_39") (pintype "passive"))
    )
    (net (code "46") (name "TDO") (class "Default")
      (node (ref "CON3") (pin "P$7") (pinfunction "TDO_P$7") (pintype "bidirectional"))
      (node (ref "U4") (pin "37") (pinfunction "37_37") (pintype "passive"))
    )
    (net (code "47") (name "TMS") (class "Default")
      (node (ref "CON3") (pin "P$1") (pinfunction "TMS_P$1") (pintype "bidirectional"))
      (node (ref "U4") (pin "38") (pinfunction "38_38") (pintype "passive"))
    )
    (net (code "48") (name "X1") (class "Default")
      (node (ref "Q2") (pin "1") (pinfunction "XIN_1") (pintype "passive"))
      (node (ref "R10") (pin "P$2") (pinfunction "P$2_P$2") (pintype "passive"))
      (node (ref "U4") (pin "42") (pinfunction "42_42") (pintype "passive"))
    )
    (net (code "49") (name "X2") (class "Default")
      (node (ref "R10") (pin "P$1") (pinfunction "P$1_P$1") (pintype "passive"))
      (node (ref "R9") (pin "P$1") (pinfunction "P$1_P$1") (pintype "passive"))
      (node (ref "U4") (pin "41") (pinfunction "41_41") (pintype "passive"))
    )
    (net (code "50") (name "XBAR4") (class "Default")
      (node (ref "J6") (pin "P$1") (pinfunction "PIN1_P$1") (pintype "bidirectional"))
      (node (ref "U4") (pin "32") (pinfunction "32_32") (pintype "passive"))
    )
    (net (code "51") (name "XBAR7") (class "Default")
      (node (ref "J5") (pin "P$1") (pinfunction "PIN1_P$1") (pintype "bidirectional"))
      (node (ref "U4") (pin "33") (pinfunction "33_33") (pintype "passive"))
    )
    (net (code "52") (name "XBAR8") (class "Default")
      (node (ref "J4") (pin "P$1") (pinfunction "PIN1_P$1") (pintype "bidirectional"))
      (node (ref "U4") (pin "34") (pinfunction "34_34") (pintype "passive"))
    )
    (net (code "53") (name "unconnected-(CON3-TRST-PadP$2)") (class "Default")
      (node (ref "CON3") (pin "P$2") (pinfunction "TRST_P$2") (pintype "bidirectional"))
    )
    (net (code "54") (name "unconnected-(U4-Pad6)") (class "Default")
      (node (ref "U4") (pin "6") (pinfunction "6_6") (pintype "passive"))
    )
    (net (code "55") (name "unconnected-(U4-Pad8)") (class "Default")
      (node (ref "U4") (pin "8") (pinfunction "8_8") (pintype "passive"))
    )
    (net (code "56") (name "unconnected-(U4-Pad10)") (class "Default")
      (node (ref "U4") (pin "10") (pinfunction "10_10") (pintype "passive"))
    )
    (net (code "57") (name "unconnected-(U4-Pad12)") (class "Default")
      (node (ref "U4") (pin "12") (pinfunction "12_12") (pintype "passive"))
    )
    (net (code "58") (name "unconnected-(U4-Pad14)") (class "Default")
      (node (ref "U4") (pin "14") (pinfunction "14_14") (pintype "passive"))
    )
    (net (code "59") (name "unconnected-(U4-Pad15)") (class "Default")
      (node (ref "U4") (pin "15") (pinfunction "15_15") (pintype "passive"))
    )
    (net (code "60") (name "unconnected-(U4-Pad18)") (class "Default")
      (node (ref "U4") (pin "18") (pinfunction "18_18") (pintype "passive"))
    )
    (net (code "61") (name "unconnected-(U4-Pad19)") (class "Default")
      (node (ref "U4") (pin "19") (pinfunction "19_19") (pintype "passive"))
    )
    (net (code "62") (name "unconnected-(U4-Pad20)") (class "Default")
      (node (ref "U4") (pin "20") (pinfunction "20_20") (pintype "passive"))
    )
    (net (code "63") (name "unconnected-(U4-Pad23)") (class "Default")
      (node (ref "U4") (pin "23") (pinfunction "23_23") (pintype "passive"))
    )
    (net (code "64") (name "unconnected-(U4-Pad24)") (class "Default")
      (node (ref "U4") (pin "24") (pinfunction "24_24") (pintype "passive"))
    )
    (net (code "65") (name "unconnected-(U4-Pad25)") (class "Default")
      (node (ref "U4") (pin "25") (pinfunction "25_25") (pintype "passive"))
    )
    (net (code "66") (name "unconnected-(U4-Pad29)") (class "Default")
      (node (ref "U4") (pin "29") (pinfunction "29_29") (pintype "passive"))
    )
    (net (code "67") (name "unconnected-(U4-Pad30)") (class "Default")
      (node (ref "U4") (pin "30") (pinfunction "30_30") (pintype "passive"))
    )
    (net (code "68") (name "unconnected-(U4-Pad31)") (class "Default")
      (node (ref "U4") (pin "31") (pinfunction "31_31") (pintype "passive"))
    )
    (net (code "69") (name "unconnected-(U4-Pad40)") (class "Default")
      (node (ref "U4") (pin "40") (pinfunction "40_40") (pintype "passive"))
    )
    (net (code "70") (name "unconnected-(U4-Pad46)") (class "Default")
      (node (ref "U4") (pin "46") (pinfunction "46_46") (pintype "passive"))
    )
    (net (code "71") (name "unconnected-(U4-Pad47)") (class "Default")
      (node (ref "U4") (pin "47") (pinfunction "47_47") (pintype "passive"))
    )
    (net (code "72") (name "unconnected-(U4-Pad53)") (class "Default")
      (node (ref "U4") (pin "53") (pinfunction "53_53") (pintype "passive"))
    )
    (net (code "73") (name "unconnected-(U4-Pad54)") (class "Default")
      (node (ref "U4") (pin "54") (pinfunction "54_54") (pintype "passive"))
    )
    (net (code "74") (name "unconnected-(U4-Pad55)") (class "Default")
      (node (ref "U4") (pin "55") (pinfunction "55_55") (pintype "passive"))
    )
    (net (code "75") (name "unconnected-(U4-Pad56)") (class "Default")
      (node (ref "U4") (pin "56") (pinfunction "56_56") (pintype "passive"))
    )
    (net (code "76") (name "unconnected-(U5-NC-Pad1)") (class "Default")
      (node (ref "U5") (pin "1") (pinfunction "NC_1") (pintype "no_connect"))
    )
    (net (code "77") (name "~{XRS}") (class "Default")
      (node (ref "C23") (pin "P$1") (pinfunction "P$1_P$1") (pintype "passive"))
      (node (ref "R16") (pin "P$2") (pinfunction "P$2_P$2") (pintype "passive"))
      (node (ref "U4") (pin "3") (pinfunction "3_3") (pintype "passive"))
      (node (ref "U5") (pin "4") (pinfunction "Y_4") (pintype "output"))
    )
  )
)
